# 2015_FDP_STRATEGIE.net
KiCad netlist of a schematic drawn in Altium Designer
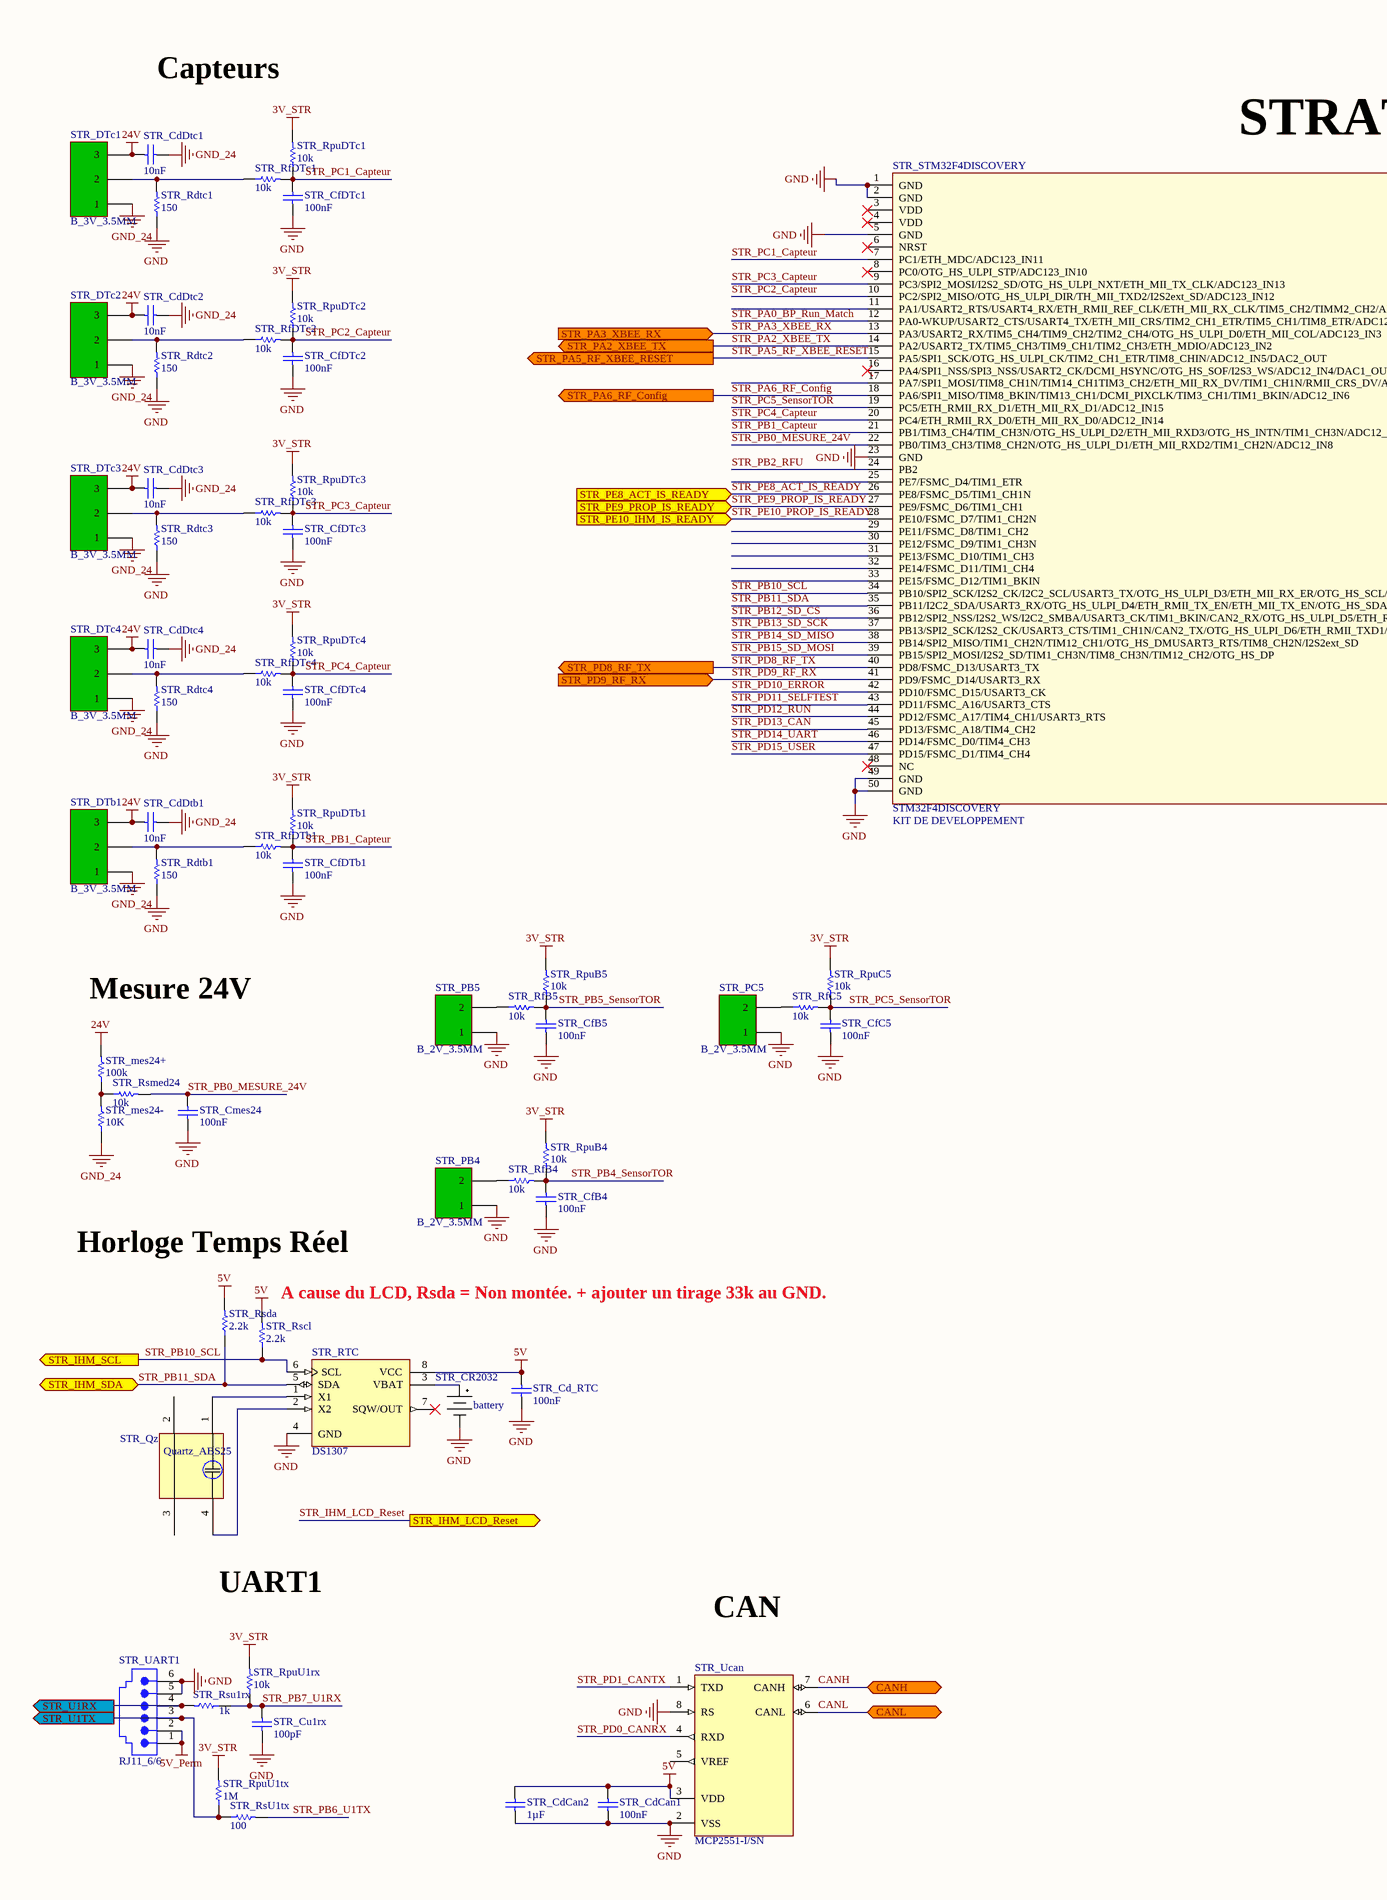
[diagram p0: 2015_FDP_STRATEGIE.SchDoc, left]
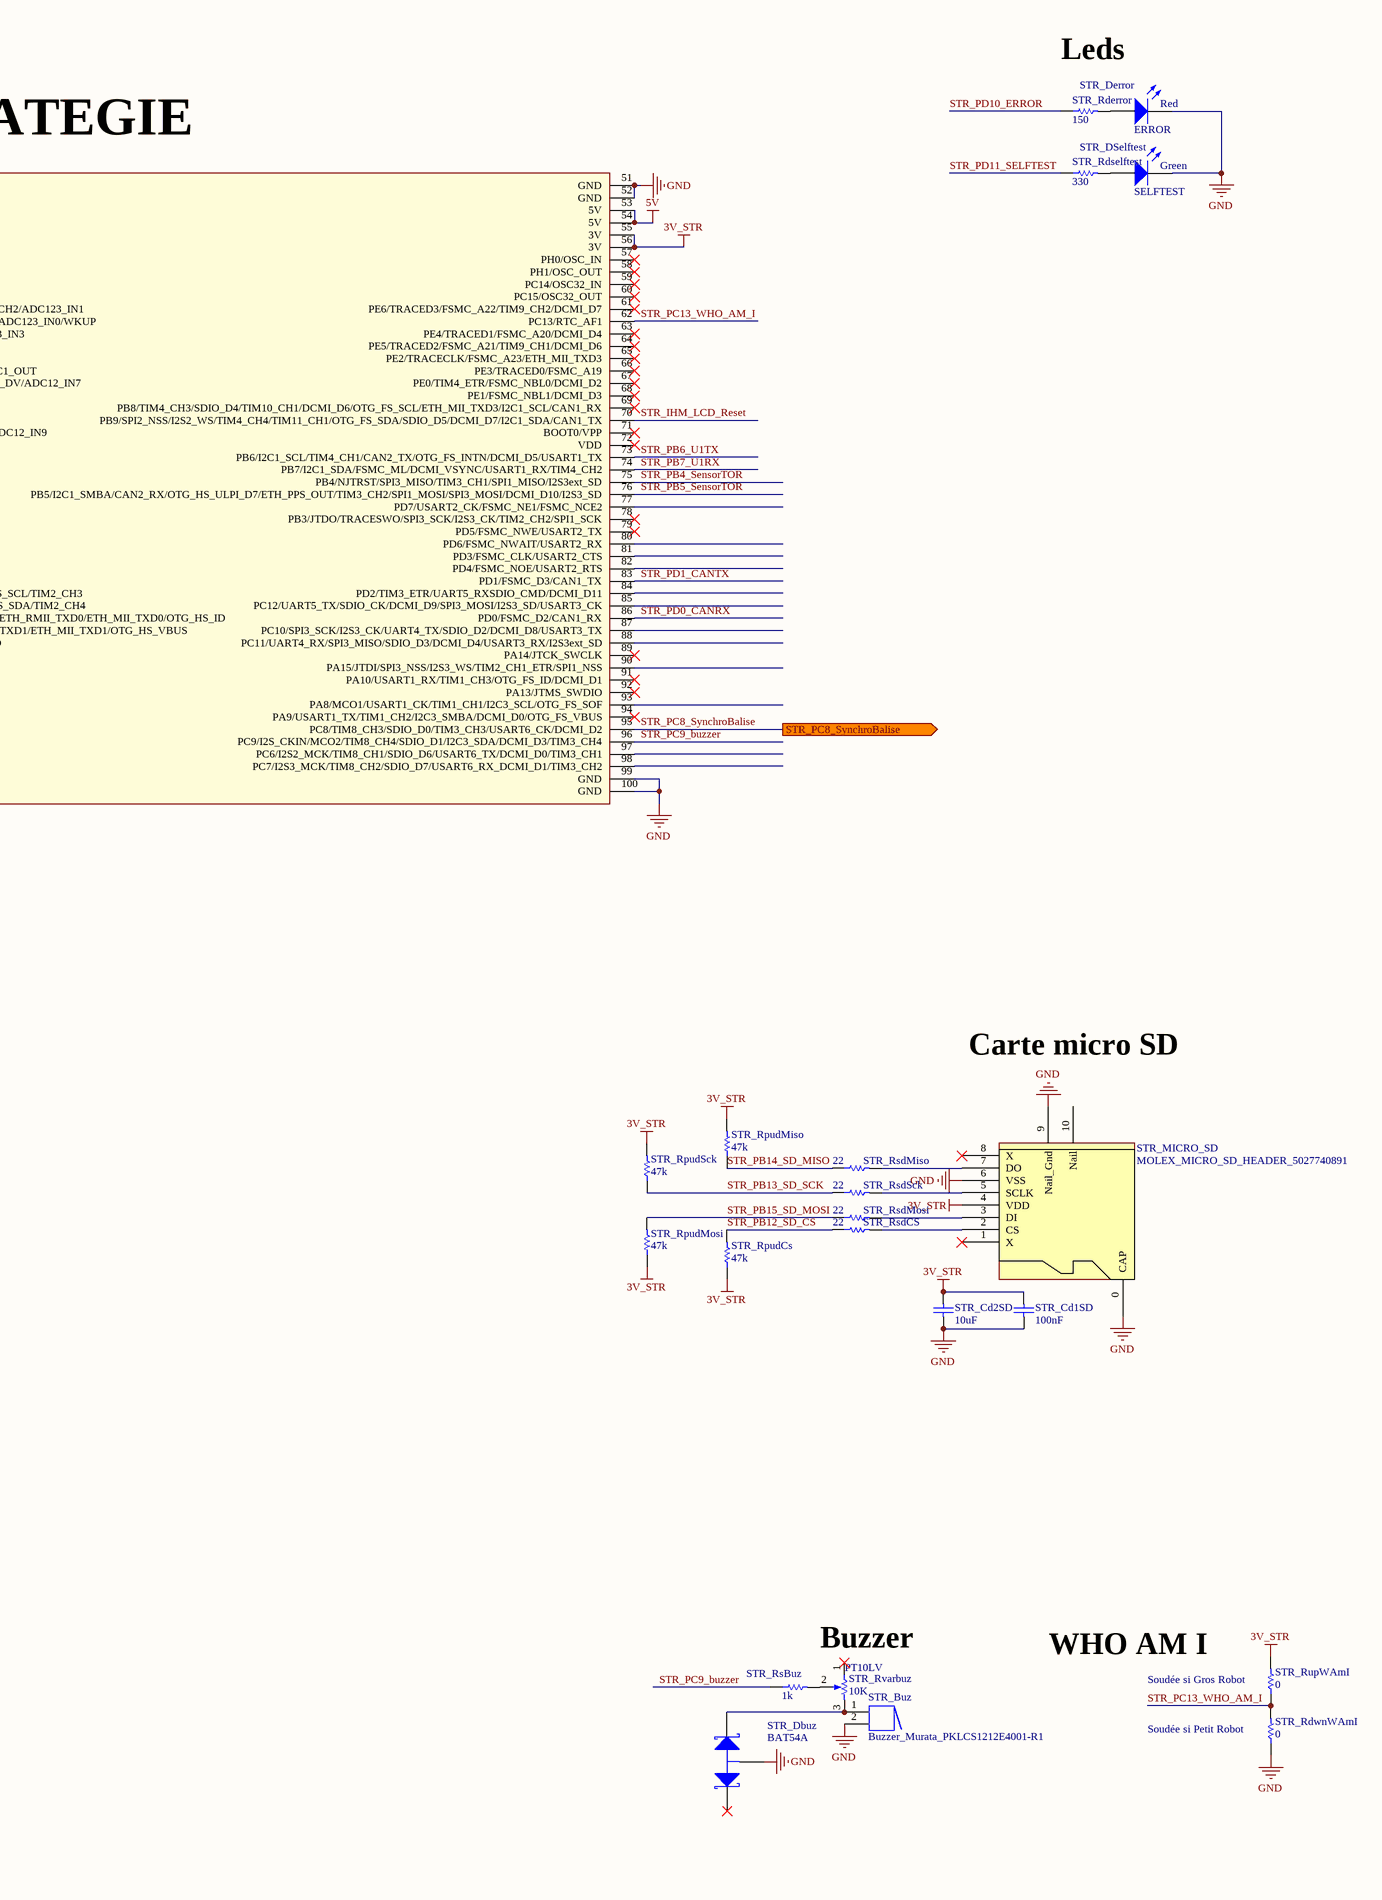
[diagram p1: 2015_FDP_STRATEGIE.SchDoc, right]

(export (version "E")
  (design (tool "Eeschema 10.0.6"))
  (components
    (comp (ref "STR_Buz")
      (value "Buzzer_Murata_PKLCS1212E4001-R1")
      (footprint "Buzzer_Murata PKLCS1212")
      (fields
        (field (name "MANUFACTURER") "MURATA")
        (field (name "MANUFACTURER PART NUMBER") "PKLCS1212E4001-R1")
      )
      (libsource (lib "DG_Buzzer") (part "Buzzer_Murata_PKLCS1212E4001-R1"))
    )
    (comp (ref "STR_Cd1SD")
      (value "100nF")
      (footprint "C0805_N")
      (description "Capacitor")
      (fields (field (name "PUBLISHER") "Altium Limited"))
      (libsource (lib "_ROBOT") (part "Condensateur"))
    )
    (comp (ref "STR_Cd2SD")
      (value "10uF")
      (footprint "C1206_N")
      (description "Capacitor")
      (fields (field (name "PUBLISHER") "Altium Limited"))
      (libsource (lib "_ROBOT") (part "Condensateur"))
    )
    (comp (ref "STR_CdCan1")
      (value "100nF")
      (footprint "C0805_N")
      (description "Capacitor")
      (fields (field (name "PUBLISHER") "Altium Limited"))
      (libsource (lib "_ROBOT") (part "Condensateur"))
    )
    (comp (ref "STR_CdCan2")
      (value "1µF")
      (footprint "C0805_N")
      (description "Capacitor")
      (fields (field (name "PUBLISHER") "Altium Limited"))
      (libsource (lib "_ROBOT") (part "Condensateur"))
    )
    (comp (ref "STR_CdDtb1")
      (value "10nF")
      (footprint "C0805_N")
      (description "Capacitor")
      (fields (field (name "PUBLISHER") "Altium Limited"))
      (libsource (lib "_ROBOT") (part "Condensateur"))
    )
    (comp (ref "STR_CdDtc1")
      (value "10nF")
      (footprint "C0805_N")
      (description "Capacitor")
      (fields (field (name "PUBLISHER") "Altium Limited"))
      (libsource (lib "_ROBOT") (part "Condensateur"))
    )
    (comp (ref "STR_CdDtc2")
      (value "10nF")
      (footprint "C0805_N")
      (description "Capacitor")
      (fields (field (name "PUBLISHER") "Altium Limited"))
      (libsource (lib "_ROBOT") (part "Condensateur"))
    )
    (comp (ref "STR_CdDtc3")
      (value "10nF")
      (footprint "C0805_N")
      (description "Capacitor")
      (fields (field (name "PUBLISHER") "Altium Limited"))
      (libsource (lib "_ROBOT") (part "Condensateur"))
    )
    (comp (ref "STR_CdDtc4")
      (value "10nF")
      (footprint "C0805_N")
      (description "Capacitor")
      (fields (field (name "PUBLISHER") "Altium Limited"))
      (libsource (lib "_ROBOT") (part "Condensateur"))
    )
    (comp (ref "STR_Cd_RTC")
      (value "100nF")
      (footprint "C0805_N")
      (description "Capacitor")
      (fields (field (name "PUBLISHER") "Altium Limited"))
      (libsource (lib "_ROBOT") (part "Condensateur"))
    )
    (comp (ref "STR_CfB4")
      (value "100nF")
      (footprint "C0805_N")
      (description "Capacitor")
      (fields (field (name "PUBLISHER") "Altium Limited"))
      (libsource (lib "_ROBOT") (part "Condensateur"))
    )
    (comp (ref "STR_CfB5")
      (value "100nF")
      (footprint "C0805_N")
      (description "Capacitor")
      (fields (field (name "PUBLISHER") "Altium Limited"))
      (libsource (lib "_ROBOT") (part "Condensateur"))
    )
    (comp (ref "STR_CfC5")
      (value "100nF")
      (footprint "C0805_N")
      (description "Capacitor")
      (fields (field (name "PUBLISHER") "Altium Limited"))
      (libsource (lib "_ROBOT") (part "Condensateur"))
    )
    (comp (ref "STR_CfDTb1")
      (value "100nF")
      (footprint "C0805_N")
      (description "Capacitor")
      (fields (field (name "PUBLISHER") "Altium Limited"))
      (libsource (lib "_ROBOT") (part "Condensateur"))
    )
    (comp (ref "STR_CfDTc1")
      (value "100nF")
      (footprint "C0805_N")
      (description "Capacitor")
      (fields (field (name "PUBLISHER") "Altium Limited"))
      (libsource (lib "_ROBOT") (part "Condensateur"))
    )
    (comp (ref "STR_CfDTc2")
      (value "100nF")
      (footprint "C0805_N")
      (description "Capacitor")
      (fields (field (name "PUBLISHER") "Altium Limited"))
      (libsource (lib "_ROBOT") (part "Condensateur"))
    )
    (comp (ref "STR_CfDTc3")
      (value "100nF")
      (footprint "C0805_N")
      (description "Capacitor")
      (fields (field (name "PUBLISHER") "Altium Limited"))
      (libsource (lib "_ROBOT") (part "Condensateur"))
    )
    (comp (ref "STR_CfDTc4")
      (value "100nF")
      (footprint "C0805_N")
      (description "Capacitor")
      (fields (field (name "PUBLISHER") "Altium Limited"))
      (libsource (lib "_ROBOT") (part "Condensateur"))
    )
    (comp (ref "STR_Cmes24")
      (value "100nF")
      (footprint "C0805_N")
      (description "Capacitor")
      (fields (field (name "PUBLISHER") "Altium Limited"))
      (libsource (lib "_ROBOT") (part "Condensateur"))
    )
    (comp (ref "STR_CR2032")
      (value "battery")
      (footprint "Pile_boutton")
      (description "Battery, Pile")
      (fields (field (name "PUBLISHER") "Jean-Philippe Oudet"))
      (libsource (lib "LibPocketTag") (part "battery"))
    )
    (comp (ref "STR_Cu1rx")
      (value "100pF")
      (footprint "C0805_N")
      (description "Capacitor")
      (fields (field (name "PUBLISHER") "Altium Limited"))
      (libsource (lib "_ROBOT") (part "Condensateur"))
    )
    (comp (ref "STR_Dbuz")
      (value "BAT54A")
      (footprint "SOT23-3N")
      (description "DIODE SCHOTTKY DOUBLE")
      (fields (field (name "MANUFACTURER") "ZETEX"))
      (libsource (lib "_ROBOT") (part "Diode Shottky double  BAT54A"))
    )
    (comp (ref "STR_Derror")
      (value "ERROR")
      (footprint "LED_0805")
      (description "Typical LED")
      (fields (field (name "PUBLISHER") "Altium Limited"))
      (libsource (lib "_ROBOT") (part "LED"))
    )
    (comp (ref "STR_DSelftest")
      (value "SELFTEST")
      (footprint "LED_0805")
      (description "Typical LED")
      (fields (field (name "PUBLISHER") "Altium Limited"))
      (libsource (lib "_ROBOT") (part "LED"))
    )
    (comp (ref "STR_DTb1")
      (value "B_3V_3.5MM")
      (footprint "BORNIER_3V_3.5MM")
      (libsource (lib "Connecteur") (part "BORNIER_3V_3.5MM"))
    )
    (comp (ref "STR_DTc1")
      (value "B_3V_3.5MM")
      (footprint "BORNIER_3V_3.5MM")
      (libsource (lib "Connecteur") (part "BORNIER_3V_3.5MM"))
    )
    (comp (ref "STR_DTc2")
      (value "B_3V_3.5MM")
      (footprint "BORNIER_3V_3.5MM")
      (libsource (lib "Connecteur") (part "BORNIER_3V_3.5MM"))
    )
    (comp (ref "STR_DTc3")
      (value "B_3V_3.5MM")
      (footprint "BORNIER_3V_3.5MM")
      (libsource (lib "Connecteur") (part "BORNIER_3V_3.5MM"))
    )
    (comp (ref "STR_DTc4")
      (value "B_3V_3.5MM")
      (footprint "BORNIER_3V_3.5MM")
      (libsource (lib "Connecteur") (part "BORNIER_3V_3.5MM"))
    )
    (comp (ref "STR_mes24+")
      (value "100k")
      (footprint "R1206_N")
      (description "Resistor")
      (fields (field (name "PUBLISHER") "Altium Limited"))
      (libsource (lib "_ROBOT") (part "Resistor"))
    )
    (comp (ref "STR_mes24-")
      (value "10K")
      (footprint "R1206_N")
      (description "Resistor")
      (fields (field (name "PUBLISHER") "Altium Limited"))
      (libsource (lib "_ROBOT") (part "Resistor"))
    )
    (comp (ref "STR_MICRO_SD")
      (value "MOLEX_MICRO_SD_HEADER_5027740891")
      (footprint "MOLEX_MICRO_SD_HEADER_5027740891")
      (libsource (lib "Connecteur") (part "MOLEX_MICRO_SD_HEADER_5027740891"))
    )
    (comp (ref "STR_PB4")
      (value "B_2V_3.5MM")
      (footprint "BORNIER_2V_3.5MM")
      (libsource (lib "Connecteur") (part "BORNIER_2V_3.5MM"))
    )
    (comp (ref "STR_PB5")
      (value "B_2V_3.5MM")
      (footprint "BORNIER_2V_3.5MM")
      (libsource (lib "Connecteur") (part "BORNIER_2V_3.5MM"))
    )
    (comp (ref "STR_PC5")
      (value "B_2V_3.5MM")
      (footprint "BORNIER_2V_3.5MM")
      (libsource (lib "Connecteur") (part "BORNIER_2V_3.5MM"))
    )
    (comp (ref "STR_Qz")
      (value "Quartz_ABS25")
      (footprint "Quartz_ABS25")
      (libsource (lib "_ROBOT") (part "Quartz_ABS25"))
    )
    (comp (ref "STR_Rderror")
      (value "150")
      (footprint "R1206_N")
      (description "Resistor")
      (fields (field (name "PUBLISHER") "Altium Limited"))
      (libsource (lib "_ROBOT") (part "Resistor"))
    )
    (comp (ref "STR_Rdselftest")
      (value "330")
      (footprint "R1206_N")
      (description "Resistor")
      (fields (field (name "PUBLISHER") "Altium Limited"))
      (libsource (lib "_ROBOT") (part "Resistor"))
    )
    (comp (ref "STR_Rdtb1")
      (value "150")
      (footprint "R1206_N")
      (description "Resistor")
      (fields (field (name "PUBLISHER") "Altium Limited"))
      (libsource (lib "_ROBOT") (part "Resistor"))
    )
    (comp (ref "STR_Rdtc1")
      (value "150")
      (footprint "R1206_N")
      (description "Resistor")
      (fields (field (name "PUBLISHER") "Altium Limited"))
      (libsource (lib "_ROBOT") (part "Resistor"))
    )
    (comp (ref "STR_Rdtc2")
      (value "150")
      (footprint "R1206_N")
      (description "Resistor")
      (fields (field (name "PUBLISHER") "Altium Limited"))
      (libsource (lib "_ROBOT") (part "Resistor"))
    )
    (comp (ref "STR_Rdtc3")
      (value "150")
      (footprint "R1206_N")
      (description "Resistor")
      (fields (field (name "PUBLISHER") "Altium Limited"))
      (libsource (lib "_ROBOT") (part "Resistor"))
    )
    (comp (ref "STR_Rdtc4")
      (value "150")
      (footprint "R1206_N")
      (description "Resistor")
      (fields (field (name "PUBLISHER") "Altium Limited"))
      (libsource (lib "_ROBOT") (part "Resistor"))
    )
    (comp (ref "STR_RdwnWAmI")
      (value "0")
      (footprint "R1206_N")
      (description "Resistor")
      (fields (field (name "PUBLISHER") "Altium Limited"))
      (libsource (lib "_ROBOT") (part "Resistor"))
    )
    (comp (ref "STR_RfB4")
      (value "10k")
      (footprint "R1206_N")
      (description "Resistor")
      (fields (field (name "PUBLISHER") "Altium Limited"))
      (libsource (lib "_ROBOT") (part "Resistor"))
    )
    (comp (ref "STR_RfB5")
      (value "10k")
      (footprint "R1206_N")
      (description "Resistor")
      (fields (field (name "PUBLISHER") "Altium Limited"))
      (libsource (lib "_ROBOT") (part "Resistor"))
    )
    (comp (ref "STR_RfC5")
      (value "10k")
      (footprint "R1206_N")
      (description "Resistor")
      (fields (field (name "PUBLISHER") "Altium Limited"))
      (libsource (lib "_ROBOT") (part "Resistor"))
    )
    (comp (ref "STR_RfDTb1")
      (value "10k")
      (footprint "R1206_N")
      (description "Resistor")
      (fields (field (name "PUBLISHER") "Altium Limited"))
      (libsource (lib "_ROBOT") (part "Resistor"))
    )
    (comp (ref "STR_RfDTc1")
      (value "10k")
      (footprint "R1206_N")
      (description "Resistor")
      (fields (field (name "PUBLISHER") "Altium Limited"))
      (libsource (lib "_ROBOT") (part "Resistor"))
    )
    (comp (ref "STR_RfDTc2")
      (value "10k")
      (footprint "R1206_N")
      (description "Resistor")
      (fields (field (name "PUBLISHER") "Altium Limited"))
      (libsource (lib "_ROBOT") (part "Resistor"))
    )
    (comp (ref "STR_RfDTc3")
      (value "10k")
      (footprint "R1206_N")
      (description "Resistor")
      (fields (field (name "PUBLISHER") "Altium Limited"))
      (libsource (lib "_ROBOT") (part "Resistor"))
    )
    (comp (ref "STR_RfDTc4")
      (value "10k")
      (footprint "R1206_N")
      (description "Resistor")
      (fields (field (name "PUBLISHER") "Altium Limited"))
      (libsource (lib "_ROBOT") (part "Resistor"))
    )
    (comp (ref "STR_RpuB4")
      (value "10k")
      (footprint "R1206_N")
      (description "Resistor")
      (fields (field (name "PUBLISHER") "Altium Limited"))
      (libsource (lib "_ROBOT") (part "Resistor"))
    )
    (comp (ref "STR_RpuB5")
      (value "10k")
      (footprint "R1206_N")
      (description "Resistor")
      (fields (field (name "PUBLISHER") "Altium Limited"))
      (libsource (lib "_ROBOT") (part "Resistor"))
    )
    (comp (ref "STR_RpuC5")
      (value "10k")
      (footprint "R1206_N")
      (description "Resistor")
      (fields (field (name "PUBLISHER") "Altium Limited"))
      (libsource (lib "_ROBOT") (part "Resistor"))
    )
    (comp (ref "STR_RpudCs")
      (value "47k")
      (footprint "R1206_N")
      (description "Resistor")
      (fields (field (name "PUBLISHER") "Altium Limited"))
      (libsource (lib "_ROBOT") (part "Resistor"))
    )
    (comp (ref "STR_RpudMiso")
      (value "47k")
      (footprint "R1206_N")
      (description "Resistor")
      (fields (field (name "PUBLISHER") "Altium Limited"))
      (libsource (lib "_ROBOT") (part "Resistor"))
    )
    (comp (ref "STR_RpudMosi")
      (value "47k")
      (footprint "R1206_N")
      (description "Resistor")
      (fields (field (name "PUBLISHER") "Altium Limited"))
      (libsource (lib "_ROBOT") (part "Resistor"))
    )
    (comp (ref "STR_RpudSck")
      (value "47k")
      (footprint "R1206_N")
      (description "Resistor")
      (fields (field (name "PUBLISHER") "Altium Limited"))
      (libsource (lib "_ROBOT") (part "Resistor"))
    )
    (comp (ref "STR_RpuDTb1")
      (value "10k")
      (footprint "R1206_N")
      (description "Resistor")
      (fields (field (name "PUBLISHER") "Altium Limited"))
      (libsource (lib "_ROBOT") (part "Resistor"))
    )
    (comp (ref "STR_RpuDTc1")
      (value "10k")
      (footprint "R1206_N")
      (description "Resistor")
      (fields (field (name "PUBLISHER") "Altium Limited"))
      (libsource (lib "_ROBOT") (part "Resistor"))
    )
    (comp (ref "STR_RpuDTc2")
      (value "10k")
      (footprint "R1206_N")
      (description "Resistor")
      (fields (field (name "PUBLISHER") "Altium Limited"))
      (libsource (lib "_ROBOT") (part "Resistor"))
    )
    (comp (ref "STR_RpuDTc3")
      (value "10k")
      (footprint "R1206_N")
      (description "Resistor")
      (fields (field (name "PUBLISHER") "Altium Limited"))
      (libsource (lib "_ROBOT") (part "Resistor"))
    )
    (comp (ref "STR_RpuDTc4")
      (value "10k")
      (footprint "R1206_N")
      (description "Resistor")
      (fields (field (name "PUBLISHER") "Altium Limited"))
      (libsource (lib "_ROBOT") (part "Resistor"))
    )
    (comp (ref "STR_RpuU1rx")
      (value "10k")
      (footprint "R1206_N")
      (description "Resistor")
      (fields (field (name "PUBLISHER") "Altium Limited"))
      (libsource (lib "_ROBOT") (part "Resistor"))
    )
    (comp (ref "STR_RpuU1tx")
      (value "1M")
      (footprint "R1206_N")
      (description "Resistor")
      (fields (field (name "PUBLISHER") "Altium Limited"))
      (libsource (lib "_ROBOT") (part "Resistor"))
    )
    (comp (ref "STR_RsBuz")
      (value "1k")
      (footprint "R1206_N")
      (description "Resistor")
      (fields (field (name "PUBLISHER") "Altium Limited"))
      (libsource (lib "_ROBOT") (part "Resistor"))
    )
    (comp (ref "STR_Rscl")
      (value "2.2k")
      (footprint "R1206_N")
      (description "Resistor")
      (fields (field (name "PUBLISHER") "Altium Limited"))
      (libsource (lib "_ROBOT") (part "Resistor"))
    )
    (comp (ref "STR_Rsda")
      (value "2.2k")
      (footprint "R1206_N")
      (description "Resistor")
      (fields (field (name "PUBLISHER") "Altium Limited"))
      (libsource (lib "_ROBOT") (part "Resistor"))
    )
    (comp (ref "STR_RsdCS")
      (value "22")
      (footprint "R1206_N")
      (description "Resistor")
      (fields (field (name "PUBLISHER") "Altium Limited"))
      (libsource (lib "_ROBOT") (part "Resistor"))
    )
    (comp (ref "STR_RsdMiso")
      (value "22")
      (footprint "R1206_N")
      (description "Resistor")
      (fields (field (name "PUBLISHER") "Altium Limited"))
      (libsource (lib "_ROBOT") (part "Resistor"))
    )
    (comp (ref "STR_RsdMosi")
      (value "22")
      (footprint "R1206_N")
      (description "Resistor")
      (fields (field (name "PUBLISHER") "Altium Limited"))
      (libsource (lib "_ROBOT") (part "Resistor"))
    )
    (comp (ref "STR_RsdSck")
      (value "22")
      (footprint "R1206_N")
      (description "Resistor")
      (fields (field (name "PUBLISHER") "Altium Limited"))
      (libsource (lib "_ROBOT") (part "Resistor"))
    )
    (comp (ref "STR_Rsmed24")
      (value "10k")
      (footprint "R1206_N")
      (description "Resistor")
      (fields (field (name "PUBLISHER") "Altium Limited"))
      (libsource (lib "_ROBOT") (part "Resistor"))
    )
    (comp (ref "STR_Rsu1rx")
      (value "1k")
      (footprint "R1206_N")
      (description "Resistor")
      (fields (field (name "PUBLISHER") "Altium Limited"))
      (libsource (lib "_ROBOT") (part "Resistor"))
    )
    (comp (ref "STR_RsU1tx")
      (value "100")
      (footprint "R1206_N")
      (description "Resistor")
      (fields (field (name "PUBLISHER") "Altium Limited"))
      (libsource (lib "_ROBOT") (part "Resistor"))
    )
    (comp (ref "STR_RTC")
      (value "DS1307")
      (footprint "SO8_N")
      (description "64 X 8 Serial Real-Time Clock")
      (fields (field (name "PUBLISHER") "Altium Limited"))
      (libsource (lib "Robot2010") (part "DS1307"))
    )
    (comp (ref "STR_RupWAmI")
      (value "0")
      (footprint "R1206_N")
      (description "Resistor")
      (fields (field (name "PUBLISHER") "Altium Limited"))
      (libsource (lib "_ROBOT") (part "Resistor"))
    )
    (comp (ref "STR_Rvarbuz")
      (value "10K")
      (footprint "TRIMMER_MONOTOUR_PT10LV")
      (description "RESISTANCE VARIABLE_TRAVERSANTE : PT10LV")
      (fields
        (field (name "TYPE") "PT10LV")
        (field (name "Comment") "RESISTANCE_VARIABLE_TRAVERSANTE : PT10LV")
      )
      (libsource (lib "composants passifs") (part "RESISTANCE_VARIABLE_TRAVERSANTE {colon} PT10LV"))
    )
    (comp (ref "STR_STM32F4DISCOVERY")
      (value "STM32F4DISCOVERY")
      (footprint "STM32_F4DISCOVERY")
      (description "KIT DE DEVELOPPEMENT POUR MICROCONTROLEUR STM32F407VGT6")
      (fields (field (name "TYPE") "KIT DE DEVELOPPEMENT"))
      (libsource (lib "circuits integres") (part "STM32F4DISCOVERY"))
    )
    (comp (ref "STR_UART1")
      (value "RJ11_6/6")
      (footprint "RJ11_6/6 - droit")
      (description "Right Angle, Standard Profile, Offset Latch DECconnect, Flangeless PCB Jack")
      (fields (field (name "PUBLISHER") "Altium Limited"))
      (libsource (lib "Connecteur") (part "RJ11_6/6"))
    )
    (comp (ref "STR_Ucan")
      (value "MCP2551-I/SN")
      (footprint "SO8_N")
      (description "High-Speed CAN Transceiver, 8-Pin SOIC, Industrial Temperature")
      (fields (field (name "PUBLISHER") "Damien Guitton"))
      (libsource (lib "Circuit intégré") (part "MCP2551-I/SN"))
    )
  )
  (nets
    (net (code "1") (name "/CANH") (class "Default")
      (node (ref "STR_Ucan") (pin "7") (pinfunction "CANH_7") (pintype "bidirectional"))
    )
    (net (code "2") (name "/CANL") (class "Default")
      (node (ref "STR_Ucan") (pin "6") (pinfunction "CANL_6") (pintype "bidirectional"))
    )
    (net (code "3") (name "/STR_IHM_LCD_Reset") (class "Default")
      (node (ref "STR_STM32F4DISCOVERY") (pin "70") (pinfunction "PB9/SPI2_NSS/I2S2_WS/TIM4_CH4/TIM11_CH1/OTG_FS_SDA/SDIO_D5/DCMI_D7/I2C1_SDA/CAN1_TX_70") (pintype "passive"))
    )
    (net (code "4") (name "/STR_PA0_BP_Run_Match") (class "Default")
      (node (ref "STR_STM32F4DISCOVERY") (pin "12") (pinfunction "PA0-WKUP/USART2_CTS/USART4_TX/ETH_MII_CRS/TIM2_CH1_ETR/TIM5_CH1/TIM8_ETR/ADC123_IN0/WKUP_12") (pintype "passive"))
    )
    (net (code "5") (name "/STR_PA2_XBEE_TX") (class "Default")
      (node (ref "STR_STM32F4DISCOVERY") (pin "14") (pinfunction "PA2/USART2_TX/TIM5_CH3/TIM9_CH1/TIM2_CH3/ETH_MDIO/ADC123_IN2_14") (pintype "passive"))
    )
    (net (code "6") (name "/STR_PA3_XBEE_RX") (class "Default")
      (node (ref "STR_STM32F4DISCOVERY") (pin "13") (pinfunction "PA3/USART2_RX/TIM5_CH4/TIM9_CH2/TIM2_CH4/OTG_HS_ULPI_D0/ETH_MII_COL/ADC123_IN3_13") (pintype "passive"))
    )
    (net (code "7") (name "/STR_PA5_RF_XBEE_RESET") (class "Default")
      (node (ref "STR_STM32F4DISCOVERY") (pin "15") (pinfunction "PA5/SPI1_SCK/OTG_HS_ULPI_CK/TIM2_CH1_ETR/TIM8_CHIN/ADC12_IN5/DAC2_OUT_15") (pintype "passive"))
    )
    (net (code "8") (name "/STR_PA6_RF_Config") (class "Default")
      (node (ref "STR_STM32F4DISCOVERY") (pin "18") (pinfunction "PA6/SPI1_MISO/TIM8_BKIN/TIM13_CH1/DCMI_PIXCLK/TIM3_CH1/TIM1_BKIN/ADC12_IN6_18") (pintype "passive"))
    )
    (net (code "9") (name "/STR_PB0_MESURE_24V") (class "Default")
      (node (ref "STR_Cmes24") (pin "2") (pinfunction "2_2") (pintype "passive"))
      (node (ref "STR_Rsmed24") (pin "2") (pinfunction "2_2") (pintype "passive"))
      (node (ref "STR_STM32F4DISCOVERY") (pin "22") (pinfunction "PB0/TIM3_CH3/TIM8_CH2N/OTG_HS_ULPI_D1/ETH_MII_RXD2/TIM1_CH2N/ADC12_IN8_22") (pintype "passive"))
    )
    (net (code "10") (name "/STR_PB1_Capteur") (class "Default")
      (node (ref "STR_CfDTb1") (pin "2") (pinfunction "2_2") (pintype "passive"))
      (node (ref "STR_RfDTb1") (pin "2") (pinfunction "2_2") (pintype "passive"))
      (node (ref "STR_RpuDTb1") (pin "1") (pinfunction "1_1") (pintype "passive"))
      (node (ref "STR_STM32F4DISCOVERY") (pin "21") (pinfunction "PB1/TIM3_CH4/TIM_CH3N/OTG_HS_ULPI_D2/ETH_MII_RXD3/OTG_HS_INTN/TIM1_CH3N/ADC12_IN9_21") (pintype "passive"))
    )
    (net (code "11") (name "/STR_PB2_RFU") (class "Default")
      (node (ref "STR_STM32F4DISCOVERY") (pin "24") (pinfunction "PB2_24") (pintype "passive"))
    )
    (net (code "12") (name "/STR_PB4_SensorTOR") (class "Default")
      (node (ref "STR_CfB4") (pin "2") (pinfunction "2_2") (pintype "passive"))
      (node (ref "STR_RfB4") (pin "2") (pinfunction "2_2") (pintype "passive"))
      (node (ref "STR_RpuB4") (pin "1") (pinfunction "1_1") (pintype "passive"))
      (node (ref "STR_STM32F4DISCOVERY") (pin "75") (pinfunction "PB4/NJTRST/SPI3_MISO/TIM3_CH1/SPI1_MISO/I2S3ext_SD_75") (pintype "passive"))
    )
    (net (code "13") (name "/STR_PB5_SensorTOR") (class "Default")
      (node (ref "STR_CfB5") (pin "2") (pinfunction "2_2") (pintype "passive"))
      (node (ref "STR_RfB5") (pin "2") (pinfunction "2_2") (pintype "passive"))
      (node (ref "STR_RpuB5") (pin "1") (pinfunction "1_1") (pintype "passive"))
      (node (ref "STR_STM32F4DISCOVERY") (pin "76") (pinfunction "PB5/I2C1_SMBA/CAN2_RX/OTG_HS_ULPI_D7/ETH_PPS_OUT/TIM3_CH2/SPI1_MOSI/SPI3_MOSI/DCMI_D10/I2S3_SD_76") (pintype "passive"))
    )
    (net (code "14") (name "/STR_PB6_U1TX") (class "Default")
      (node (ref "STR_RsU1tx") (pin "2") (pinfunction "2_2") (pintype "passive"))
      (node (ref "STR_STM32F4DISCOVERY") (pin "73") (pinfunction "PB6/I2C1_SCL/TIM4_CH1/CAN2_TX/OTG_FS_INTN/DCMI_D5/USART1_TX_73") (pintype "passive"))
    )
    (net (code "15") (name "/STR_PB7_U1RX") (class "Default")
      (node (ref "STR_Cu1rx") (pin "2") (pinfunction "2_2") (pintype "passive"))
      (node (ref "STR_RpuU1rx") (pin "1") (pinfunction "1_1") (pintype "passive"))
      (node (ref "STR_Rsu1rx") (pin "1") (pinfunction "1_1") (pintype "passive"))
      (node (ref "STR_STM32F4DISCOVERY") (pin "74") (pinfunction "PB7/I2C1_SDA/FSMC_ML/DCMI_VSYNC/USART1_RX/TIM4_CH2_74") (pintype "passive"))
    )
    (net (code "16") (name "/STR_PB10_SCL") (class "Default")
      (node (ref "STR_RTC") (pin "6") (pinfunction "SCL_6") (pintype "input"))
      (node (ref "STR_Rscl") (pin "1") (pinfunction "1_1") (pintype "passive"))
      (node (ref "STR_STM32F4DISCOVERY") (pin "34") (pinfunction "PB10/SPI2_SCK/I2S2_CK/I2C2_SCL/USART3_TX/OTG_HS_ULPI_D3/ETH_MII_RX_ER/OTG_HS_SCL/TIM2_CH3_34") (pintype "passive"))
    )
    (net (code "17") (name "/STR_PB11_SDA") (class "Default")
      (node (ref "STR_RTC") (pin "5") (pinfunction "SDA_5") (pintype "bidirectional"))
      (node (ref "STR_Rsda") (pin "1") (pinfunction "1_1") (pintype "passive"))
      (node (ref "STR_STM32F4DISCOVERY") (pin "35") (pinfunction "PB11/I2C2_SDA/USART3_RX/OTG_HS_ULPI_D4/ETH_RMII_TX_EN/ETH_MII_TX_EN/OTG_HS_SDA/TIM2_CH4_35") (pintype "passive"))
    )
    (net (code "18") (name "/STR_PB12_SD_CS") (class "Default")
      (node (ref "STR_RpudCs") (pin "2") (pinfunction "2_2") (pintype "passive"))
      (node (ref "STR_RsdCS") (pin "1") (pinfunction "1_1") (pintype "passive"))
      (node (ref "STR_STM32F4DISCOVERY") (pin "36") (pinfunction "PB12/SPI2_NSS/I2S2_WS/I2C2_SMBA/USART3_CK/TIM1_BKIN/CAN2_RX/OTG_HS_ULPI_D5/ETH_RMII_TXD0/ETH_MII_TXD0/OTG_HS_ID_36") (pintype "passive"))
    )
    (net (code "19") (name "/STR_PB13_SD_SCK") (class "Default")
      (node (ref "STR_RpudSck") (pin "1") (pinfunction "1_1") (pintype "passive"))
      (node (ref "STR_RsdSck") (pin "1") (pinfunction "1_1") (pintype "passive"))
      (node (ref "STR_STM32F4DISCOVERY") (pin "37") (pinfunction "PB13/SPI2_SCK/I2S2_CK/USART3_CTS/TIM1_CH1N/CAN2_TX/OTG_HS_ULPI_D6/ETH_RMII_TXD1/ETH_MII_TXD1/OTG_HS_VBUS_37") (pintype "passive"))
    )
    (net (code "20") (name "/STR_PB14_SD_MISO") (class "Default")
      (node (ref "STR_RpudMiso") (pin "1") (pinfunction "1_1") (pintype "passive"))
      (node (ref "STR_RsdMiso") (pin "1") (pinfunction "1_1") (pintype "passive"))
      (node (ref "STR_STM32F4DISCOVERY") (pin "38") (pinfunction "PB14/SPI2_MISO/TIM1_CH2N/TIM12_CH1/OTG_HS_DMUSART3_RTS/TIM8_CH2N/I2S2ext_SD_38") (pintype "passive"))
    )
    (net (code "21") (name "/STR_PB15_SD_MOSI") (class "Default")
      (node (ref "STR_RpudMosi") (pin "2") (pinfunction "2_2") (pintype "passive"))
      (node (ref "STR_RsdMosi") (pin "1") (pinfunction "1_1") (pintype "passive"))
      (node (ref "STR_STM32F4DISCOVERY") (pin "39") (pinfunction "PB15/SPI2_MOSI/I2S2_SD/TIM1_CH3N/TIM8_CH3N/TIM12_CH2/OTG_HS_DP_39") (pintype "passive"))
    )
    (net (code "22") (name "/STR_PC1_Capteur") (class "Default")
      (node (ref "STR_CfDTc1") (pin "2") (pinfunction "2_2") (pintype "passive"))
      (node (ref "STR_RfDTc1") (pin "2") (pinfunction "2_2") (pintype "passive"))
      (node (ref "STR_RpuDTc1") (pin "1") (pinfunction "1_1") (pintype "passive"))
      (node (ref "STR_STM32F4DISCOVERY") (pin "7") (pinfunction "PC1/ETH_MDC/ADC123_IN11_7") (pintype "passive"))
    )
    (net (code "23") (name "/STR_PC2_Capteur") (class "Default")
      (node (ref "STR_CfDTc2") (pin "2") (pinfunction "2_2") (pintype "passive"))
      (node (ref "STR_RfDTc2") (pin "2") (pinfunction "2_2") (pintype "passive"))
      (node (ref "STR_RpuDTc2") (pin "1") (pinfunction "1_1") (pintype "passive"))
      (node (ref "STR_STM32F4DISCOVERY") (pin "10") (pinfunction "PC2/SPI2_MISO/OTG_HS_ULPI_DIR/TH_MII_TXD2/I2S2ext_SD/ADC123_IN12_10") (pintype "passive"))
    )
    (net (code "24") (name "/STR_PC3_Capteur") (class "Default")
      (node (ref "STR_CfDTc3") (pin "2") (pinfunction "2_2") (pintype "passive"))
      (node (ref "STR_RfDTc3") (pin "2") (pinfunction "2_2") (pintype "passive"))
      (node (ref "STR_RpuDTc3") (pin "1") (pinfunction "1_1") (pintype "passive"))
      (node (ref "STR_STM32F4DISCOVERY") (pin "9") (pinfunction "PC3/SPI2_MOSI/I2S2_SD/OTG_HS_ULPI_NXT/ETH_MII_TX_CLK/ADC123_IN13_9") (pintype "passive"))
    )
    (net (code "25") (name "/STR_PC4_Capteur") (class "Default")
      (node (ref "STR_CfDTc4") (pin "2") (pinfunction "2_2") (pintype "passive"))
      (node (ref "STR_RfDTc4") (pin "2") (pinfunction "2_2") (pintype "passive"))
      (node (ref "STR_RpuDTc4") (pin "1") (pinfunction "1_1") (pintype "passive"))
      (node (ref "STR_STM32F4DISCOVERY") (pin "20") (pinfunction "PC4/ETH_RMII_RX_D0/ETH_MII_RX_D0/ADC12_IN14_20") (pintype "passive"))
    )
    (net (code "26") (name "/STR_PC5_SensorTOR") (class "Default")
      (node (ref "STR_CfC5") (pin "2") (pinfunction "2_2") (pintype "passive"))
      (node (ref "STR_RfC5") (pin "2") (pinfunction "2_2") (pintype "passive"))
      (node (ref "STR_RpuC5") (pin "1") (pinfunction "1_1") (pintype "passive"))
      (node (ref "STR_STM32F4DISCOVERY") (pin "19") (pinfunction "PC5/ETH_RMII_RX_D1/ETH_MII_RX_D1/ADC12_IN15_19") (pintype "passive"))
    )
    (net (code "27") (name "/STR_PC8_SynchroBalise") (class "Default")
      (node (ref "STR_STM32F4DISCOVERY") (pin "95") (pinfunction "PC8/TIM8_CH3/SDIO_D0/TIM3_CH3/USART6_CK/DCMI_D2_95") (pintype "passive"))
    )
    (net (code "28") (name "/STR_PC9_buzzer") (class "Default")
      (node (ref "STR_RsBuz") (pin "1") (pinfunction "1_1") (pintype "passive"))
      (node (ref "STR_STM32F4DISCOVERY") (pin "96") (pinfunction "PC9/I2S_CKIN/MCO2/TIM8_CH4/SDIO_D1/I2C3_SDA/DCMI_D3/TIM3_CH4_96") (pintype "passive"))
    )
    (net (code "29") (name "/STR_PC13_WHO_AM_I") (class "Default")
      (node (ref "STR_RdwnWAmI") (pin "2") (pinfunction "2_2") (pintype "passive"))
      (node (ref "STR_RupWAmI") (pin "1") (pinfunction "1_1") (pintype "passive"))
      (node (ref "STR_STM32F4DISCOVERY") (pin "62") (pinfunction "PC13/RTC_AF1_62") (pintype "passive"))
    )
    (net (code "30") (name "/STR_PD0_CANRX") (class "Default")
      (node (ref "STR_STM32F4DISCOVERY") (pin "86") (pinfunction "PD0/FSMC_D2/CAN1_RX_86") (pintype "passive"))
      (node (ref "STR_Ucan") (pin "4") (pinfunction "RXD_4") (pintype "output"))
    )
    (net (code "31") (name "/STR_PD1_CANTX") (class "Default")
      (node (ref "STR_STM32F4DISCOVERY") (pin "83") (pinfunction "PD1/FSMC_D3/CAN1_TX_83") (pintype "passive"))
      (node (ref "STR_Ucan") (pin "1") (pinfunction "TXD_1") (pintype "input"))
    )
    (net (code "32") (name "/STR_PD8_RF_TX") (class "Default")
      (node (ref "STR_STM32F4DISCOVERY") (pin "40") (pinfunction "PD8/FSMC_D13/USART3_TX_40") (pintype "passive"))
    )
    (net (code "33") (name "/STR_PD9_RF_RX") (class "Default")
      (node (ref "STR_STM32F4DISCOVERY") (pin "41") (pinfunction "PD9/FSMC_D14/USART3_RX_41") (pintype "passive"))
    )
    (net (code "34") (name "/STR_PD10_ERROR") (class "Default")
      (node (ref "STR_Rderror") (pin "1") (pinfunction "1_1") (pintype "passive"))
      (node (ref "STR_STM32F4DISCOVERY") (pin "42") (pinfunction "PD10/FSMC_D15/USART3_CK_42") (pintype "passive"))
    )
    (net (code "35") (name "/STR_PD11_SELFTEST") (class "Default")
      (node (ref "STR_Rdselftest") (pin "1") (pinfunction "1_1") (pintype "passive"))
      (node (ref "STR_STM32F4DISCOVERY") (pin "43") (pinfunction "PD11/FSMC_A16/USART3_CTS_43") (pintype "passive"))
    )
    (net (code "36") (name "/STR_PD12_RUN") (class "Default")
      (node (ref "STR_STM32F4DISCOVERY") (pin "44") (pinfunction "PD12/FSMC_A17/TIM4_CH1/USART3_RTS_44") (pintype "passive"))
    )
    (net (code "37") (name "/STR_PD13_CAN") (class "Default")
      (node (ref "STR_STM32F4DISCOVERY") (pin "45") (pinfunction "PD13/FSMC_A18/TIM4_CH2_45") (pintype "passive"))
    )
    (net (code "38") (name "/STR_PD14_UART") (class "Default")
      (node (ref "STR_STM32F4DISCOVERY") (pin "46") (pinfunction "PD14/FSMC_D0/TIM4_CH3_46") (pintype "passive"))
    )
    (net (code "39") (name "/STR_PD15_USER") (class "Default")
      (node (ref "STR_STM32F4DISCOVERY") (pin "47") (pinfunction "PD15/FSMC_D1/TIM4_CH4_47") (pintype "passive"))
    )
    (net (code "40") (name "/STR_PE8_ACT_IS_READY") (class "Default")
      (node (ref "STR_STM32F4DISCOVERY") (pin "26") (pinfunction "PE8/FSMC_D5/TIM1_CH1N_26") (pintype "passive"))
    )
    (net (code "41") (name "/STR_PE9_PROP_IS_READY") (class "Default")
      (node (ref "STR_STM32F4DISCOVERY") (pin "27") (pinfunction "PE9/FSMC_D6/TIM1_CH1_27") (pintype "passive"))
    )
    (net (code "42") (name "/STR_PE10_PROP_IS_READY") (class "Default")
      (node (ref "STR_STM32F4DISCOVERY") (pin "28") (pinfunction "PE10/FSMC_D7/TIM1_CH2N_28") (pintype "passive"))
    )
    (net (code "43") (name "/STR_U1RX") (class "Default")
      (node (ref "STR_Rsu1rx") (pin "2") (pinfunction "2_2") (pintype "passive"))
      (node (ref "STR_UART1") (pin "4") (pinfunction "4_4") (pintype "passive"))
    )
    (net (code "44") (name "/STR_U1TX") (class "Default")
      (node (ref "STR_RpuU1tx") (pin "1") (pinfunction "1_1") (pintype "passive"))
      (node (ref "STR_RsU1tx") (pin "1") (pinfunction "1_1") (pintype "passive"))
      (node (ref "STR_UART1") (pin "3") (pinfunction "3_3") (pintype "passive"))
    )
    (net (code "45") (name "3V_STR") (class "Default")
      (node (ref "STR_Cd1SD") (pin "2") (pinfunction "2_2") (pintype "passive"))
      (node (ref "STR_Cd2SD") (pin "2") (pinfunction "2_2") (pintype "passive"))
      (node (ref "STR_MICRO_SD") (pin "4") (pinfunction "VDD_4") (pintype "passive"))
      (node (ref "STR_RpuB4") (pin "2") (pinfunction "2_2") (pintype "passive"))
      (node (ref "STR_RpuB5") (pin "2") (pinfunction "2_2") (pintype "passive"))
      (node (ref "STR_RpuC5") (pin "2") (pinfunction "2_2") (pintype "passive"))
      (node (ref "STR_RpuDTb1") (pin "2") (pinfunction "2_2") (pintype "passive"))
      (node (ref "STR_RpuDTc1") (pin "2") (pinfunction "2_2") (pintype "passive"))
      (node (ref "STR_RpuDTc2") (pin "2") (pinfunction "2_2") (pintype "passive"))
      (node (ref "STR_RpuDTc3") (pin "2") (pinfunction "2_2") (pintype "passive"))
      (node (ref "STR_RpuDTc4") (pin "2") (pinfunction "2_2") (pintype "passive"))
      (node (ref "STR_RpuU1rx") (pin "2") (pinfunction "2_2") (pintype "passive"))
      (node (ref "STR_RpuU1tx") (pin "2") (pinfunction "2_2") (pintype "passive"))
      (node (ref "STR_RpudCs") (pin "1") (pinfunction "1_1") (pintype "passive"))
      (node (ref "STR_RpudMiso") (pin "2") (pinfunction "2_2") (pintype "passive"))
      (node (ref "STR_RpudMosi") (pin "1") (pinfunction "1_1") (pintype "passive"))
      (node (ref "STR_RpudSck") (pin "2") (pinfunction "2_2") (pintype "passive"))
      (node (ref "STR_RupWAmI") (pin "2") (pinfunction "2_2") (pintype "passive"))
      (node (ref "STR_STM32F4DISCOVERY") (pin "55") (pinfunction "3V_55") (pintype "passive"))
      (node (ref "STR_STM32F4DISCOVERY") (pin "56") (pinfunction "3V_56") (pintype "passive"))
    )
    (net (code "46") (name "5V") (class "Default")
      (node (ref "STR_CdCan1") (pin "2") (pinfunction "2_2") (pintype "passive"))
      (node (ref "STR_CdCan2") (pin "2") (pinfunction "2_2") (pintype "passive"))
      (node (ref "STR_Cd_RTC") (pin "1") (pinfunction "1_1") (pintype "passive"))
      (node (ref "STR_RTC") (pin "8") (pinfunction "VCC_8") (pintype "power_in"))
      (node (ref "STR_Rscl") (pin "2") (pinfunction "2_2") (pintype "passive"))
      (node (ref "STR_Rsda") (pin "2") (pinfunction "2_2") (pintype "passive"))
      (node (ref "STR_STM32F4DISCOVERY") (pin "53") (pinfunction "5V_53") (pintype "passive"))
      (node (ref "STR_STM32F4DISCOVERY") (pin "54") (pinfunction "5V_54") (pintype "passive"))
      (node (ref "STR_Ucan") (pin "3") (pinfunction "VDD_3") (pintype "power_in"))
    )
    (net (code "47") (name "5V_Perm") (class "Default")
      (node (ref "STR_UART1") (pin "1") (pinfunction "1_1") (pintype "passive"))
      (node (ref "STR_UART1") (pin "2") (pinfunction "2_2") (pintype "passive"))
    )
    (net (code "48") (name "24V") (class "Default")
      (node (ref "STR_CdDtb1") (pin "2") (pinfunction "2_2") (pintype "passive"))
      (node (ref "STR_CdDtc1") (pin "2") (pinfunction "2_2") (pintype "passive"))
      (node (ref "STR_CdDtc2") (pin "2") (pinfunction "2_2") (pintype "passive"))
      (node (ref "STR_CdDtc3") (pin "2") (pinfunction "2_2") (pintype "passive"))
      (node (ref "STR_CdDtc4") (pin "2") (pinfunction "2_2") (pintype "passive"))
      (node (ref "STR_DTb1") (pin "3") (pinfunction "3_3") (pintype "passive"))
      (node (ref "STR_DTc1") (pin "3") (pinfunction "3_3") (pintype "passive"))
      (node (ref "STR_DTc2") (pin "3") (pinfunction "3_3") (pintype "passive"))
      (node (ref "STR_DTc3") (pin "3") (pinfunction "3_3") (pintype "passive"))
      (node (ref "STR_DTc4") (pin "3") (pinfunction "3_3") (pintype "passive"))
      (node (ref "STR_mes24+") (pin "2") (pinfunction "2_2") (pintype "passive"))
    )
    (net (code "49") (name "GND") (class "Default")
      (node (ref "STR_Buz") (pin "2") (pinfunction "2_2") (pintype "passive"))
      (node (ref "STR_CR2032") (pin "2") (pinfunction "-_2") (pintype "power_in"))
      (node (ref "STR_Cd1SD") (pin "1") (pinfunction "1_1") (pintype "passive"))
      (node (ref "STR_Cd2SD") (pin "1") (pinfunction "1_1") (pintype "passive"))
      (node (ref "STR_CdCan1") (pin "1") (pinfunction "1_1") (pintype "passive"))
      (node (ref "STR_CdCan2") (pin "1") (pinfunction "1_1") (pintype "passive"))
      (node (ref "STR_Cd_RTC") (pin "2") (pinfunction "2_2") (pintype "passive"))
      (node (ref "STR_CfB4") (pin "1") (pinfunction "1_1") (pintype "passive"))
      (node (ref "STR_CfB5") (pin "1") (pinfunction "1_1") (pintype "passive"))
      (node (ref "STR_CfC5") (pin "1") (pinfunction "1_1") (pintype "passive"))
      (node (ref "STR_CfDTb1") (pin "1") (pinfunction "1_1") (pintype "passive"))
      (node (ref "STR_CfDTc1") (pin "1") (pinfunction "1_1") (pintype "passive"))
      (node (ref "STR_CfDTc2") (pin "1") (pinfunction "1_1") (pintype "passive"))
      (node (ref "STR_CfDTc3") (pin "1") (pinfunction "1_1") (pintype "passive"))
      (node (ref "STR_CfDTc4") (pin "1") (pinfunction "1_1") (pintype "passive"))
      (node (ref "STR_Cmes24") (pin "1") (pinfunction "1_1") (pintype "passive"))
      (node (ref "STR_Cu1rx") (pin "1") (pinfunction "1_1") (pintype "passive"))
      (node (ref "STR_DSelftest") (pin "2") (pinfunction "K_2") (pintype "passive"))
      (node (ref "STR_Dbuz") (pin "3") (pinfunction "A_3") (pintype "passive"))
      (node (ref "STR_Derror") (pin "2") (pinfunction "K_2") (pintype "passive"))
      (node (ref "STR_MICRO_SD") (pin "0") (pinfunction "CAP_0") (pintype "passive"))
      (node (ref "STR_MICRO_SD") (pin "6") (pinfunction "VSS_6") (pintype "passive"))
      (node (ref "STR_MICRO_SD") (pin "9") (pinfunction "Nail_Gnd_9") (pintype "passive"))
      (node (ref "STR_PB4") (pin "1") (pinfunction "1_1") (pintype "passive"))
      (node (ref "STR_PB5") (pin "1") (pinfunction "1_1") (pintype "passive"))
      (node (ref "STR_PC5") (pin "1") (pinfunction "1_1") (pintype "passive"))
      (node (ref "STR_RTC") (pin "4") (pinfunction "GND_4") (pintype "power_in"))
      (node (ref "STR_Rdtb1") (pin "1") (pinfunction "1_1") (pintype "passive"))
      (node (ref "STR_Rdtc1") (pin "1") (pinfunction "1_1") (pintype "passive"))
      (node (ref "STR_Rdtc2") (pin "1") (pinfunction "1_1") (pintype "passive"))
      (node (ref "STR_Rdtc3") (pin "1") (pinfunction "1_1") (pintype "passive"))
      (node (ref "STR_Rdtc4") (pin "1") (pinfunction "1_1") (pintype "passive"))
      (node (ref "STR_RdwnWAmI") (pin "1") (pinfunction "1_1") (pintype "passive"))
      (node (ref "STR_STM32F4DISCOVERY") (pin "1") (pinfunction "GND_1") (pintype "passive"))
      (node (ref "STR_STM32F4DISCOVERY") (pin "100") (pinfunction "GND_100") (pintype "passive"))
      (node (ref "STR_STM32F4DISCOVERY") (pin "2") (pinfunction "GND_2") (pintype "passive"))
      (node (ref "STR_STM32F4DISCOVERY") (pin "23") (pinfunction "GND_23") (pintype "passive"))
      (node (ref "STR_STM32F4DISCOVERY") (pin "49") (pinfunction "GND_49") (pintype "passive"))
      (node (ref "STR_STM32F4DISCOVERY") (pin "5") (pinfunction "GND_5") (pintype "passive"))
      (node (ref "STR_STM32F4DISCOVERY") (pin "50") (pinfunction "GND_50") (pintype "passive"))
      (node (ref "STR_STM32F4DISCOVERY") (pin "51") (pinfunction "GND_51") (pintype "passive"))
      (node (ref "STR_STM32F4DISCOVERY") (pin "52") (pinfunction "GND_52") (pintype "passive"))
      (node (ref "STR_STM32F4DISCOVERY") (pin "99") (pinfunction "GND_99") (pintype "passive"))
      (node (ref "STR_UART1") (pin "5") (pinfunction "5_5") (pintype "passive"))
      (node (ref "STR_UART1") (pin "6") (pinfunction "6_6") (pintype "passive"))
      (node (ref "STR_Ucan") (pin "2") (pinfunction "VSS_2") (pintype "power_in"))
      (node (ref "STR_Ucan") (pin "8") (pinfunction "RS_8") (pintype "input"))
    )
    (net (code "50") (name "GND_24") (class "Default")
      (node (ref "STR_CdDtb1") (pin "1") (pinfunction "1_1") (pintype "passive"))
      (node (ref "STR_CdDtc1") (pin "1") (pinfunction "1_1") (pintype "passive"))
      (node (ref "STR_CdDtc2") (pin "1") (pinfunction "1_1") (pintype "passive"))
      (node (ref "STR_CdDtc3") (pin "1") (pinfunction "1_1") (pintype "passive"))
      (node (ref "STR_CdDtc4") (pin "1") (pinfunction "1_1") (pintype "passive"))
      (node (ref "STR_DTb1") (pin "1") (pinfunction "1_1") (pintype "passive"))
      (node (ref "STR_DTc1") (pin "1") (pinfunction "1_1") (pintype "passive"))
      (node (ref "STR_DTc2") (pin "1") (pinfunction "1_1") (pintype "passive"))
      (node (ref "STR_DTc3") (pin "1") (pinfunction "1_1") (pintype "passive"))
      (node (ref "STR_DTc4") (pin "1") (pinfunction "1_1") (pintype "passive"))
      (node (ref "STR_mes24-") (pin "1") (pinfunction "1_1") (pintype "passive"))
    )
    (net (code "51") (name "Net-(STR_CR2032-+)") (class "Default")
      (node (ref "STR_CR2032") (pin "1") (pinfunction "+_1") (pintype "power_in"))
      (node (ref "STR_RTC") (pin "3") (pinfunction "VBAT_3") (pintype "power_in"))
    )
    (net (code "52") (name "Net-(STR_DSelftest-A)") (class "Default")
      (node (ref "STR_DSelftest") (pin "1") (pinfunction "A_1") (pintype "passive"))
      (node (ref "STR_Rdselftest") (pin "2") (pinfunction "2_2") (pintype "passive"))
    )
    (net (code "53") (name "Net-(STR_DTb1-Pad2)") (class "Default")
      (node (ref "STR_DTb1") (pin "2") (pinfunction "2_2") (pintype "passive"))
      (node (ref "STR_Rdtb1") (pin "2") (pinfunction "2_2") (pintype "passive"))
      (node (ref "STR_RfDTb1") (pin "1") (pinfunction "1_1") (pintype "passive"))
    )
    (net (code "54") (name "Net-(STR_DTc1-Pad2)") (class "Default")
      (node (ref "STR_DTc1") (pin "2") (pinfunction "2_2") (pintype "passive"))
      (node (ref "STR_Rdtc1") (pin "2") (pinfunction "2_2") (pintype "passive"))
      (node (ref "STR_RfDTc1") (pin "1") (pinfunction "1_1") (pintype "passive"))
    )
    (net (code "55") (name "Net-(STR_DTc2-Pad2)") (class "Default")
      (node (ref "STR_DTc2") (pin "2") (pinfunction "2_2") (pintype "passive"))
      (node (ref "STR_Rdtc2") (pin "2") (pinfunction "2_2") (pintype "passive"))
      (node (ref "STR_RfDTc2") (pin "1") (pinfunction "1_1") (pintype "passive"))
    )
    (net (code "56") (name "Net-(STR_DTc3-Pad2)") (class "Default")
      (node (ref "STR_DTc3") (pin "2") (pinfunction "2_2") (pintype "passive"))
      (node (ref "STR_Rdtc3") (pin "2") (pinfunction "2_2") (pintype "passive"))
      (node (ref "STR_RfDTc3") (pin "1") (pinfunction "1_1") (pintype "passive"))
    )
    (net (code "57") (name "Net-(STR_DTc4-Pad2)") (class "Default")
      (node (ref "STR_DTc4") (pin "2") (pinfunction "2_2") (pintype "passive"))
      (node (ref "STR_Rdtc4") (pin "2") (pinfunction "2_2") (pintype "passive"))
      (node (ref "STR_RfDTc4") (pin "1") (pinfunction "1_1") (pintype "passive"))
    )
    (net (code "58") (name "Net-(STR_Dbuz-K1)") (class "Default")
      (node (ref "STR_Buz") (pin "1") (pinfunction "1_1") (pintype "passive"))
      (node (ref "STR_Dbuz") (pin "1") (pinfunction "K1_1") (pintype "passive"))
      (node (ref "STR_Rvarbuz") (pin "3") (pinfunction "3_3") (pintype "passive"))
    )
    (net (code "59") (name "Net-(STR_Derror-A)") (class "Default")
      (node (ref "STR_Derror") (pin "1") (pinfunction "A_1") (pintype "passive"))
      (node (ref "STR_Rderror") (pin "2") (pinfunction "2_2") (pintype "passive"))
    )
    (net (code "60") (name "Net-(STR_MICRO_SD-CS)") (class "Default")
      (node (ref "STR_MICRO_SD") (pin "2") (pinfunction "CS_2") (pintype "passive"))
      (node (ref "STR_RsdCS") (pin "2") (pinfunction "2_2") (pintype "passive"))
    )
    (net (code "61") (name "Net-(STR_MICRO_SD-DI)") (class "Default")
      (node (ref "STR_MICRO_SD") (pin "3") (pinfunction "DI_3") (pintype "passive"))
      (node (ref "STR_RsdMosi") (pin "2") (pinfunction "2_2") (pintype "passive"))
    )
    (net (code "62") (name "Net-(STR_MICRO_SD-DO)") (class "Default")
      (node (ref "STR_MICRO_SD") (pin "7") (pinfunction "DO_7") (pintype "passive"))
      (node (ref "STR_RsdMiso") (pin "2") (pinfunction "2_2") (pintype "passive"))
    )
    (net (code "63") (name "Net-(STR_MICRO_SD-SCLK)") (class "Default")
      (node (ref "STR_MICRO_SD") (pin "5") (pinfunction "SCLK_5") (pintype "passive"))
      (node (ref "STR_RsdSck") (pin "2") (pinfunction "2_2") (pintype "passive"))
    )
    (net (code "64") (name "Net-(STR_PB4-Pad2)") (class "Default")
      (node (ref "STR_PB4") (pin "2") (pinfunction "2_2") (pintype "passive"))
      (node (ref "STR_RfB4") (pin "1") (pinfunction "1_1") (pintype "passive"))
    )
    (net (code "65") (name "Net-(STR_PB5-Pad2)") (class "Default")
      (node (ref "STR_PB5") (pin "2") (pinfunction "2_2") (pintype "passive"))
      (node (ref "STR_RfB5") (pin "1") (pinfunction "1_1") (pintype "passive"))
    )
    (net (code "66") (name "Net-(STR_PC5-Pad2)") (class "Default")
      (node (ref "STR_PC5") (pin "2") (pinfunction "2_2") (pintype "passive"))
      (node (ref "STR_RfC5") (pin "1") (pinfunction "1_1") (pintype "passive"))
    )
    (net (code "67") (name "Net-(STR_RTC-X1)") (class "Default")
      (node (ref "STR_Qz") (pin "1") (pinfunction "1_1") (pintype "passive"))
      (node (ref "STR_RTC") (pin "1") (pinfunction "X1_1") (pintype "input"))
    )
    (net (code "68") (name "Net-(STR_RTC-X2)") (class "Default")
      (node (ref "STR_Qz") (pin "4") (pinfunction "4_4") (pintype "passive"))
      (node (ref "STR_RTC") (pin "2") (pinfunction "X2_2") (pintype "input"))
    )
    (net (code "69") (name "Net-(STR_RsBuz-Pad2)") (class "Default")
      (node (ref "STR_RsBuz") (pin "2") (pinfunction "2_2") (pintype "passive"))
      (node (ref "STR_Rvarbuz") (pin "2") (pinfunction "2_2") (pintype "passive"))
    )
    (net (code "70") (name "Net-(STR_Rsmed24-Pad1)") (class "Default")
      (node (ref "STR_Rsmed24") (pin "1") (pinfunction "1_1") (pintype "passive"))
      (node (ref "STR_mes24+") (pin "1") (pinfunction "1_1") (pintype "passive"))
      (node (ref "STR_mes24-") (pin "2") (pinfunction "2_2") (pintype "passive"))
    )
    (net (code "71") (name "unconnected-(STR_Dbuz-K2-Pad2)") (class "Default")
      (node (ref "STR_Dbuz") (pin "2") (pinfunction "K2_2") (pintype "passive+no_connect"))
    )
    (net (code "72") (name "unconnected-(STR_MICRO_SD-Nail-Pad10)") (class "Default")
      (node (ref "STR_MICRO_SD") (pin "10") (pinfunction "Nail_10") (pintype "passive"))
    )
    (net (code "73") (name "unconnected-(STR_MICRO_SD-X-Pad1)") (class "Default")
      (node (ref "STR_MICRO_SD") (pin "1") (pinfunction "X_1") (pintype "passive+no_connect"))
    )
    (net (code "74") (name "unconnected-(STR_MICRO_SD-X-Pad8)") (class "Default")
      (node (ref "STR_MICRO_SD") (pin "8") (pinfunction "X_8") (pintype "passive+no_connect"))
    )
    (net (code "75") (name "unconnected-(STR_Qz-Pad2)") (class "Default")
      (node (ref "STR_Qz") (pin "2") (pinfunction "2_2") (pintype "passive"))
    )
    (net (code "76") (name "unconnected-(STR_Qz-Pad3)") (class "Default")
      (node (ref "STR_Qz") (pin "3") (pinfunction "3_3") (pintype "passive"))
    )
    (net (code "77") (name "unconnected-(STR_RTC-SQW{slash}OUT-Pad7)") (class "Default")
      (node (ref "STR_RTC") (pin "7") (pinfunction "SQW/OUT_7") (pintype "output+no_connect"))
    )
    (net (code "78") (name "unconnected-(STR_Rvarbuz-Pad1)") (class "Default")
      (node (ref "STR_Rvarbuz") (pin "1") (pinfunction "1_1") (pintype "passive+no_connect"))
    )
    (net (code "79") (name "unconnected-(STR_STM32F4DISCOVERY-BOOT0{slash}VPP-Pad71)") (class "Default")
      (node (ref "STR_STM32F4DISCOVERY") (pin "71") (pinfunction "BOOT0/VPP_71") (pintype "passive+no_connect"))
    )
    (net (code "80") (name "unconnected-(STR_STM32F4DISCOVERY-NC-Pad48)") (class "Default")
      (node (ref "STR_STM32F4DISCOVERY") (pin "48") (pinfunction "NC_48") (pintype "passive+no_connect"))
    )
    (net (code "81") (name "unconnected-(STR_STM32F4DISCOVERY-NRST-Pad6)") (class "Default")
      (node (ref "STR_STM32F4DISCOVERY") (pin "6") (pinfunction "NRST_6") (pintype "passive+no_connect"))
    )
    (net (code "82") (name "unconnected-(STR_STM32F4DISCOVERY-PA1{slash}USART2_RTS{slash}USART4_RX{slash}ETH_RMII_REF_CLK{slash}ETH_MII_RX_CLK{slash}TIM5_CH2{slash}TIMM2_CH2{slash}ADC123_IN1-Pad11)") (class "Default")
      (node (ref "STR_STM32F4DISCOVERY") (pin "11") (pinfunction "PA1/USART2_RTS/USART4_RX/ETH_RMII_REF_CLK/ETH_MII_RX_CLK/TIM5_CH2/TIMM2_CH2/ADC123_IN1_11") (pintype "passive"))
    )
    (net (code "83") (name "unconnected-(STR_STM32F4DISCOVERY-PA4{slash}SPI1_NSS{slash}SPI3_NSS{slash}USART2_CK{slash}DCMI_HSYNC{slash}OTG_HS_SOF{slash}I2S3_WS{slash}ADC12_IN4{slash}DAC1_OUT-Pad16)") (class "Default")
      (node (ref "STR_STM32F4DISCOVERY") (pin "16") (pinfunction "PA4/SPI1_NSS/SPI3_NSS/USART2_CK/DCMI_HSYNC/OTG_HS_SOF/I2S3_WS/ADC12_IN4/DAC1_OUT_16") (pintype "passive+no_connect"))
    )
    (net (code "84") (name "unconnected-(STR_STM32F4DISCOVERY-PA7{slash}SPI1_MOSI{slash}TIM8_CH1N{slash}TIM14_CH1TIM3_CH2{slash}ETH_MII_RX_DV{slash}TIM1_CH1N{slash}RMII_CRS_DV{slash}ADC12_IN7-Pad17)") (class "Default")
      (node (ref "STR_STM32F4DISCOVERY") (pin "17") (pinfunction "PA7/SPI1_MOSI/TIM8_CH1N/TIM14_CH1TIM3_CH2/ETH_MII_RX_DV/TIM1_CH1N/RMII_CRS_DV/ADC12_IN7_17") (pintype "passive"))
    )
    (net (code "85") (name "unconnected-(STR_STM32F4DISCOVERY-PA8{slash}MCO1{slash}USART1_CK{slash}TIM1_CH1{slash}I2C3_SCL{slash}OTG_FS_SOF-Pad93)") (class "Default")
      (node (ref "STR_STM32F4DISCOVERY") (pin "93") (pinfunction "PA8/MCO1/USART1_CK/TIM1_CH1/I2C3_SCL/OTG_FS_SOF_93") (pintype "passive"))
    )
    (net (code "86") (name "unconnected-(STR_STM32F4DISCOVERY-PA9{slash}USART1_TX{slash}TIM1_CH2{slash}I2C3_SMBA{slash}DCMI_D0{slash}OTG_FS_VBUS-Pad94)") (class "Default")
      (node (ref "STR_STM32F4DISCOVERY") (pin "94") (pinfunction "PA9/USART1_TX/TIM1_CH2/I2C3_SMBA/DCMI_D0/OTG_FS_VBUS_94") (pintype "passive+no_connect"))
    )
    (net (code "87") (name "unconnected-(STR_STM32F4DISCOVERY-PA10{slash}USART1_RX{slash}TIM1_CH3{slash}OTG_FS_ID{slash}DCMI_D1-Pad91)") (class "Default")
      (node (ref "STR_STM32F4DISCOVERY") (pin "91") (pinfunction "PA10/USART1_RX/TIM1_CH3/OTG_FS_ID/DCMI_D1_91") (pintype "passive+no_connect"))
    )
    (net (code "88") (name "unconnected-(STR_STM32F4DISCOVERY-PA13{slash}JTMS_SWDIO-Pad92)") (class "Default")
      (node (ref "STR_STM32F4DISCOVERY") (pin "92") (pinfunction "PA13/JTMS_SWDIO_92") (pintype "passive+no_connect"))
    )
    (net (code "89") (name "unconnected-(STR_STM32F4DISCOVERY-PA14{slash}JTCK_SWCLK-Pad89)") (class "Default")
      (node (ref "STR_STM32F4DISCOVERY") (pin "89") (pinfunction "PA14/JTCK_SWCLK_89") (pintype "passive+no_connect"))
    )
    (net (code "90") (name "unconnected-(STR_STM32F4DISCOVERY-PA15{slash}JTDI{slash}SPI3_NSS{slash}I2S3_WS{slash}TIM2_CH1_ETR{slash}SPI1_NSS-Pad90)") (class "Default")
      (node (ref "STR_STM32F4DISCOVERY") (pin "90") (pinfunction "PA15/JTDI/SPI3_NSS/I2S3_WS/TIM2_CH1_ETR/SPI1_NSS_90") (pintype "passive"))
    )
    (net (code "91") (name "unconnected-(STR_STM32F4DISCOVERY-PB3{slash}JTDO{slash}TRACESWO{slash}SPI3_SCK{slash}I2S3_CK{slash}TIM2_CH2{slash}SPI1_SCK-Pad78)") (class "Default")
      (node (ref "STR_STM32F4DISCOVERY") (pin "78") (pinfunction "PB3/JTDO/TRACESWO/SPI3_SCK/I2S3_CK/TIM2_CH2/SPI1_SCK_78") (pintype "passive+no_connect"))
    )
    (net (code "92") (name "unconnected-(STR_STM32F4DISCOVERY-PB8{slash}TIM4_CH3{slash}SDIO_D4{slash}TIM10_CH1{slash}DCMI_D6{slash}OTG_FS_SCL{slash}ETH_MII_TXD3{slash}I2C1_SCL{slash}CAN1_RX-Pad69)") (class "Default")
      (node (ref "STR_STM32F4DISCOVERY") (pin "69") (pinfunction "PB8/TIM4_CH3/SDIO_D4/TIM10_CH1/DCMI_D6/OTG_FS_SCL/ETH_MII_TXD3/I2C1_SCL/CAN1_RX_69") (pintype "passive+no_connect"))
    )
    (net (code "93") (name "unconnected-(STR_STM32F4DISCOVERY-PC0{slash}OTG_HS_ULPI_STP{slash}ADC123_IN10-Pad8)") (class "Default")
      (node (ref "STR_STM32F4DISCOVERY") (pin "8") (pinfunction "PC0/OTG_HS_ULPI_STP/ADC123_IN10_8") (pintype "passive+no_connect"))
    )
    (net (code "94") (name "unconnected-(STR_STM32F4DISCOVERY-PC6{slash}I2S2_MCK{slash}TIM8_CH1{slash}SDIO_D6{slash}USART6_TX{slash}DCMI_D0{slash}TIM3_CH1-Pad97)") (class "Default")
      (node (ref "STR_STM32F4DISCOVERY") (pin "97") (pinfunction "PC6/I2S2_MCK/TIM8_CH1/SDIO_D6/USART6_TX/DCMI_D0/TIM3_CH1_97") (pintype "passive"))
    )
    (net (code "95") (name "unconnected-(STR_STM32F4DISCOVERY-PC7{slash}I2S3_MCK{slash}TIM8_CH2{slash}SDIO_D7{slash}USART6_RX_DCMI_D1{slash}TIM3_CH2-Pad98)") (class "Default")
      (node (ref "STR_STM32F4DISCOVERY") (pin "98") (pinfunction "PC7/I2S3_MCK/TIM8_CH2/SDIO_D7/USART6_RX_DCMI_D1/TIM3_CH2_98") (pintype "passive"))
    )
    (net (code "96") (name "unconnected-(STR_STM32F4DISCOVERY-PC10{slash}SPI3_SCK{slash}I2S3_CK{slash}UART4_TX{slash}SDIO_D2{slash}DCMI_D8{slash}USART3_TX-Pad87)") (class "Default")
      (node (ref "STR_STM32F4DISCOVERY") (pin "87") (pinfunction "PC10/SPI3_SCK/I2S3_CK/UART4_TX/SDIO_D2/DCMI_D8/USART3_TX_87") (pintype "passive"))
    )
    (net (code "97") (name "unconnected-(STR_STM32F4DISCOVERY-PC11{slash}UART4_RX{slash}SPI3_MISO{slash}SDIO_D3{slash}DCMI_D4{slash}USART3_RX{slash}I2S3ext_SD-Pad88)") (class "Default")
      (node (ref "STR_STM32F4DISCOVERY") (pin "88") (pinfunction "PC11/UART4_RX/SPI3_MISO/SDIO_D3/DCMI_D4/USART3_RX/I2S3ext_SD_88") (pintype "passive"))
    )
    (net (code "98") (name "unconnected-(STR_STM32F4DISCOVERY-PC12{slash}UART5_TX{slash}SDIO_CK{slash}DCMI_D9{slash}SPI3_MOSI{slash}I2S3_SD{slash}USART3_CK-Pad85)") (class "Default")
      (node (ref "STR_STM32F4DISCOVERY") (pin "85") (pinfunction "PC12/UART5_TX/SDIO_CK/DCMI_D9/SPI3_MOSI/I2S3_SD/USART3_CK_85") (pintype "passive"))
    )
    (net (code "99") (name "unconnected-(STR_STM32F4DISCOVERY-PC14{slash}OSC32_IN-Pad59)") (class "Default")
      (node (ref "STR_STM32F4DISCOVERY") (pin "59") (pinfunction "PC14/OSC32_IN_59") (pintype "passive+no_connect"))
    )
    (net (code "100") (name "unconnected-(STR_STM32F4DISCOVERY-PC15{slash}OSC32_OUT-Pad60)") (class "Default")
      (node (ref "STR_STM32F4DISCOVERY") (pin "60") (pinfunction "PC15/OSC32_OUT_60") (pintype "passive+no_connect"))
    )
    (net (code "101") (name "unconnected-(STR_STM32F4DISCOVERY-PD2{slash}TIM3_ETR{slash}UART5_RXSDIO_CMD{slash}DCMI_D11-Pad84)") (class "Default")
      (node (ref "STR_STM32F4DISCOVERY") (pin "84") (pinfunction "PD2/TIM3_ETR/UART5_RXSDIO_CMD/DCMI_D11_84") (pintype "passive"))
    )
    (net (code "102") (name "unconnected-(STR_STM32F4DISCOVERY-PD3{slash}FSMC_CLK{slash}USART2_CTS-Pad81)") (class "Default")
      (node (ref "STR_STM32F4DISCOVERY") (pin "81") (pinfunction "PD3/FSMC_CLK/USART2_CTS_81") (pintype "passive"))
    )
    (net (code "103") (name "unconnected-(STR_STM32F4DISCOVERY-PD4{slash}FSMC_NOE{slash}USART2_RTS-Pad82)") (class "Default")
      (node (ref "STR_STM32F4DISCOVERY") (pin "82") (pinfunction "PD4/FSMC_NOE/USART2_RTS_82") (pintype "passive"))
    )
    (net (code "104") (name "unconnected-(STR_STM32F4DISCOVERY-PD5{slash}FSMC_NWE{slash}USART2_TX-Pad79)") (class "Default")
      (node (ref "STR_STM32F4DISCOVERY") (pin "79") (pinfunction "PD5/FSMC_NWE/USART2_TX_79") (pintype "passive+no_connect"))
    )
    (net (code "105") (name "unconnected-(STR_STM32F4DISCOVERY-PD6{slash}FSMC_NWAIT{slash}USART2_RX-Pad80)") (class "Default")
      (node (ref "STR_STM32F4DISCOVERY") (pin "80") (pinfunction "PD6/FSMC_NWAIT/USART2_RX_80") (pintype "passive"))
    )
    (net (code "106") (name "unconnected-(STR_STM32F4DISCOVERY-PD7{slash}USART2_CK{slash}FSMC_NE1{slash}FSMC_NCE2-Pad77)") (class "Default")
      (node (ref "STR_STM32F4DISCOVERY") (pin "77") (pinfunction "PD7/USART2_CK/FSMC_NE1/FSMC_NCE2_77") (pintype "passive"))
    )
    (net (code "107") (name "unconnected-(STR_STM32F4DISCOVERY-PE0{slash}TIM4_ETR{slash}FSMC_NBL0{slash}DCMI_D2-Pad67)") (class "Default")
      (node (ref "STR_STM32F4DISCOVERY") (pin "67") (pinfunction "PE0/TIM4_ETR/FSMC_NBL0/DCMI_D2_67") (pintype "passive+no_connect"))
    )
    (net (code "108") (name "unconnected-(STR_STM32F4DISCOVERY-PE1{slash}FSMC_NBL1{slash}DCMI_D3-Pad68)") (class "Default")
      (node (ref "STR_STM32F4DISCOVERY") (pin "68") (pinfunction "PE1/FSMC_NBL1/DCMI_D3_68") (pintype "passive+no_connect"))
    )
    (net (code "109") (name "unconnected-(STR_STM32F4DISCOVERY-PE2{slash}TRACECLK{slash}FSMC_A23{slash}ETH_MII_TXD3-Pad65)") (class "Default")
      (node (ref "STR_STM32F4DISCOVERY") (pin "65") (pinfunction "PE2/TRACECLK/FSMC_A23/ETH_MII_TXD3_65") (pintype "passive+no_connect"))
    )
    (net (code "110") (name "unconnected-(STR_STM32F4DISCOVERY-PE3{slash}TRACED0{slash}FSMC_A19-Pad66)") (class "Default")
      (node (ref "STR_STM32F4DISCOVERY") (pin "66") (pinfunction "PE3/TRACED0/FSMC_A19_66") (pintype "passive+no_connect"))
    )
    (net (code "111") (name "unconnected-(STR_STM32F4DISCOVERY-PE4{slash}TRACED1{slash}FSMC_A20{slash}DCMI_D4-Pad63)") (class "Default")
      (node (ref "STR_STM32F4DISCOVERY") (pin "63") (pinfunction "PE4/TRACED1/FSMC_A20/DCMI_D4_63") (pintype "passive+no_connect"))
    )
    (net (code "112") (name "unconnected-(STR_STM32F4DISCOVERY-PE5{slash}TRACED2{slash}FSMC_A21{slash}TIM9_CH1{slash}DCMI_D6-Pad64)") (class "Default")
      (node (ref "STR_STM32F4DISCOVERY") (pin "64") (pinfunction "PE5/TRACED2/FSMC_A21/TIM9_CH1/DCMI_D6_64") (pintype "passive+no_connect"))
    )
    (net (code "113") (name "unconnected-(STR_STM32F4DISCOVERY-PE6{slash}TRACED3{slash}FSMC_A22{slash}TIM9_CH2{slash}DCMI_D7-Pad61)") (class "Default")
      (node (ref "STR_STM32F4DISCOVERY") (pin "61") (pinfunction "PE6/TRACED3/FSMC_A22/TIM9_CH2/DCMI_D7_61") (pintype "passive+no_connect"))
    )
    (net (code "114") (name "unconnected-(STR_STM32F4DISCOVERY-PE7{slash}FSMC_D4{slash}TIM1_ETR-Pad25)") (class "Default")
      (node (ref "STR_STM32F4DISCOVERY") (pin "25") (pinfunction "PE7/FSMC_D4/TIM1_ETR_25") (pintype "passive"))
    )
    (net (code "115") (name "unconnected-(STR_STM32F4DISCOVERY-PE11{slash}FSMC_D8{slash}TIM1_CH2-Pad29)") (class "Default")
      (node (ref "STR_STM32F4DISCOVERY") (pin "29") (pinfunction "PE11/FSMC_D8/TIM1_CH2_29") (pintype "passive"))
    )
    (net (code "116") (name "unconnected-(STR_STM32F4DISCOVERY-PE12{slash}FSMC_D9{slash}TIM1_CH3N-Pad30)") (class "Default")
      (node (ref "STR_STM32F4DISCOVERY") (pin "30") (pinfunction "PE12/FSMC_D9/TIM1_CH3N_30") (pintype "passive"))
    )
    (net (code "117") (name "unconnected-(STR_STM32F4DISCOVERY-PE13{slash}FSMC_D10{slash}TIM1_CH3-Pad31)") (class "Default")
      (node (ref "STR_STM32F4DISCOVERY") (pin "31") (pinfunction "PE13/FSMC_D10/TIM1_CH3_31") (pintype "passive"))
    )
    (net (code "118") (name "unconnected-(STR_STM32F4DISCOVERY-PE14{slash}FSMC_D11{slash}TIM1_CH4-Pad32)") (class "Default")
      (node (ref "STR_STM32F4DISCOVERY") (pin "32") (pinfunction "PE14/FSMC_D11/TIM1_CH4_32") (pintype "passive"))
    )
    (net (code "119") (name "unconnected-(STR_STM32F4DISCOVERY-PE15{slash}FSMC_D12{slash}TIM1_BKIN-Pad33)") (class "Default")
      (node (ref "STR_STM32F4DISCOVERY") (pin "33") (pinfunction "PE15/FSMC_D12/TIM1_BKIN_33") (pintype "passive"))
    )
    (net (code "120") (name "unconnected-(STR_STM32F4DISCOVERY-PH0{slash}OSC_IN-Pad57)") (class "Default")
      (node (ref "STR_STM32F4DISCOVERY") (pin "57") (pinfunction "PH0/OSC_IN_57") (pintype "passive+no_connect"))
    )
    (net (code "121") (name "unconnected-(STR_STM32F4DISCOVERY-PH1{slash}OSC_OUT-Pad58)") (class "Default")
      (node (ref "STR_STM32F4DISCOVERY") (pin "58") (pinfunction "PH1/OSC_OUT_58") (pintype "passive+no_connect"))
    )
    (net (code "122") (name "unconnected-(STR_STM32F4DISCOVERY-VDD-Pad3)") (class "Default")
      (node (ref "STR_STM32F4DISCOVERY") (pin "3") (pinfunction "VDD_3") (pintype "passive+no_connect"))
    )
    (net (code "123") (name "unconnected-(STR_STM32F4DISCOVERY-VDD-Pad4)") (class "Default")
      (node (ref "STR_STM32F4DISCOVERY") (pin "4") (pinfunction "VDD_4") (pintype "passive+no_connect"))
    )
    (net (code "124") (name "unconnected-(STR_STM32F4DISCOVERY-VDD-Pad72)") (class "Default")
      (node (ref "STR_STM32F4DISCOVERY") (pin "72") (pinfunction "VDD_72") (pintype "passive+no_connect"))
    )
    (net (code "125") (name "unconnected-(STR_Ucan-VREF-Pad5)") (class "Default")
      (node (ref "STR_Ucan") (pin "5") (pinfunction "VREF_5") (pintype "output"))
    )
  )
)
